# Temp_sensor_can.net
KiCad netlist of a schematic drawn in Altium Designer
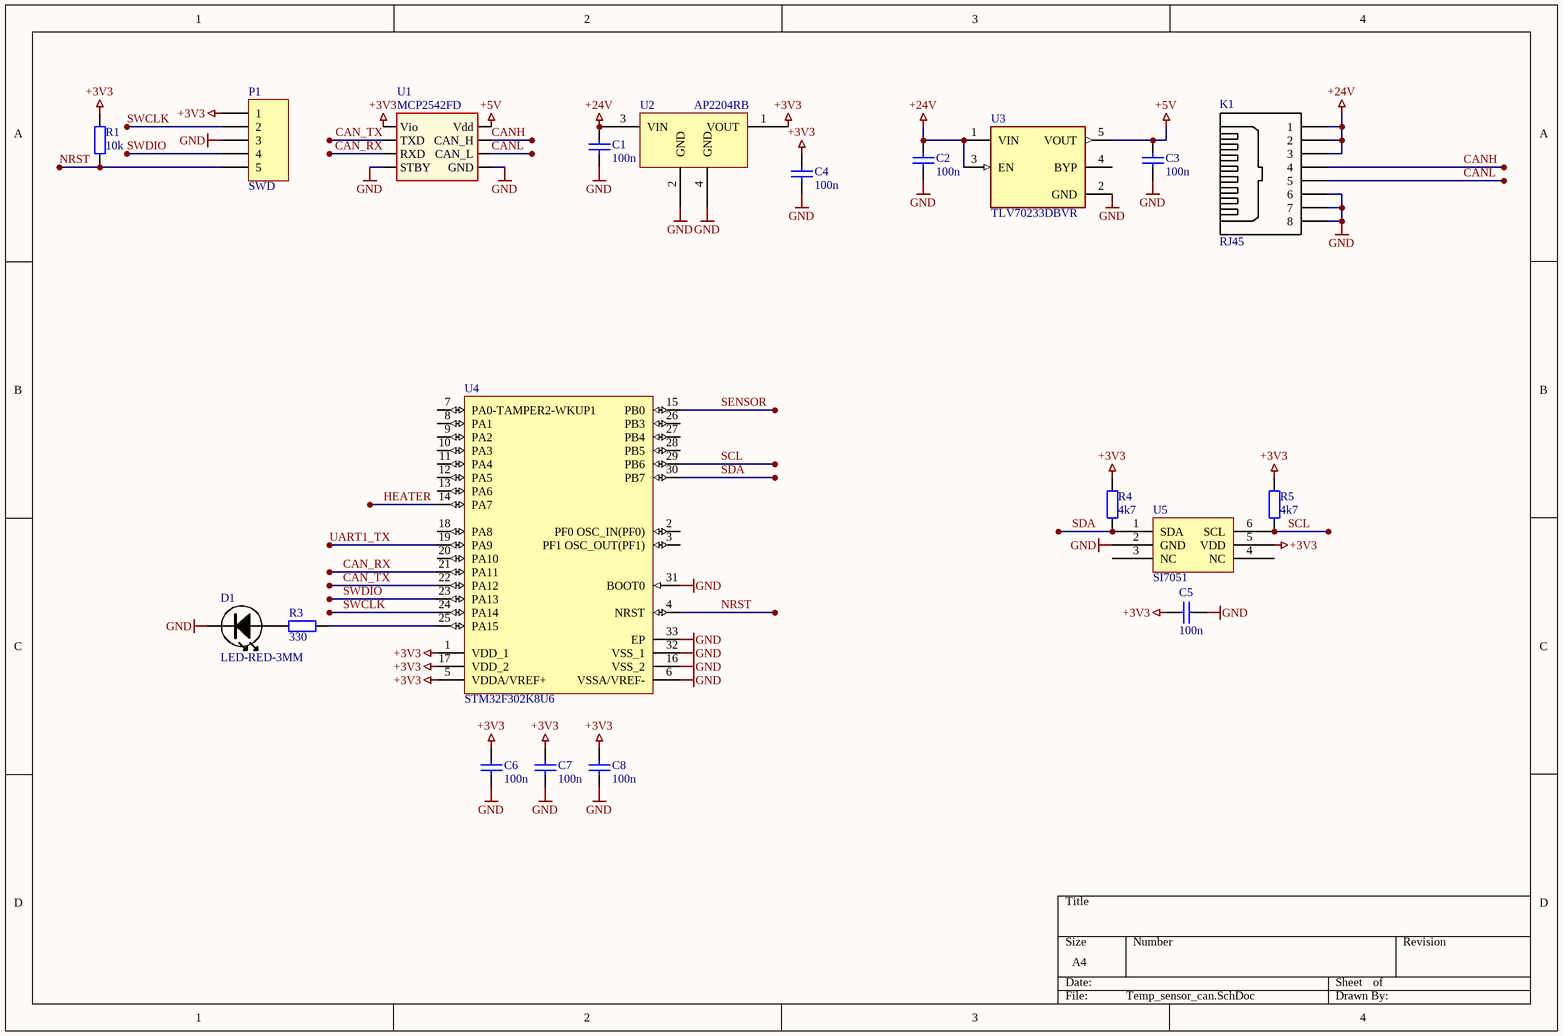
[diagram p0: Temp_sensor_can.SchDoc]

(export (version "E")
  (design (tool "Eeschema 10.0.6"))
  (components
    (comp (ref "C1")
      (value "100n")
      (footprint "0603C-GENERIC")
      (description "Capacitor")
      (fields (field (name "Comment") "Cap") (field (name "PUBLISHER") "Altium Limited"))
      (libsource (lib "Miscellaneous Devices") (part "Cap"))
    )
    (comp (ref "C2")
      (value "100n")
      (footprint "0603C-GENERIC")
      (description "Capacitor")
      (fields (field (name "Comment") "Cap") (field (name "PUBLISHER") "Altium Limited"))
      (libsource (lib "Miscellaneous Devices") (part "Cap"))
    )
    (comp (ref "C3")
      (value "100n")
      (footprint "0603C-GENERIC")
      (description "Capacitor")
      (fields (field (name "Comment") "Cap") (field (name "PUBLISHER") "Altium Limited"))
      (libsource (lib "Miscellaneous Devices") (part "Cap"))
    )
    (comp (ref "C4")
      (value "100n")
      (footprint "0603C-GENERIC")
      (description "Capacitor")
      (fields (field (name "Comment") "Cap") (field (name "PUBLISHER") "Altium Limited"))
      (libsource (lib "Miscellaneous Devices") (part "Cap"))
    )
    (comp (ref "C5")
      (value "100n")
      (footprint "0603C-GENERIC")
      (description "Capacitor")
      (fields (field (name "Comment") "Cap") (field (name "PUBLISHER") "Altium Limited"))
      (libsource (lib "Miscellaneous Devices") (part "Cap"))
    )
    (comp (ref "C6")
      (value "100n")
      (footprint "0603C-GENERIC")
      (description "Capacitor")
      (fields (field (name "Comment") "Cap") (field (name "PUBLISHER") "Altium Limited"))
      (libsource (lib "Miscellaneous Devices") (part "Cap"))
    )
    (comp (ref "C7")
      (value "100n")
      (footprint "0603C-GENERIC")
      (description "Capacitor")
      (fields (field (name "Comment") "Cap") (field (name "PUBLISHER") "Altium Limited"))
      (libsource (lib "Miscellaneous Devices") (part "Cap"))
    )
    (comp (ref "C8")
      (value "100n")
      (footprint "0603C-GENERIC")
      (description "Capacitor")
      (fields (field (name "Comment") "Cap") (field (name "PUBLISHER") "Altium Limited"))
      (libsource (lib "Miscellaneous Devices") (part "Cap"))
    )
    (comp (ref "D1")
      (value "LED-RED-3MM")
      (footprint "LED-3MM-GREEN")
      (description "LED-GREEN-3MM")
      (libsource (lib "vh_altium_library") (part "LED-GREEN-3MM"))
    )
    (comp (ref "K1")
      (value "RJ45")
      (footprint "rj45 - edge")
      (libsource (lib "vh_altium_library") (part "RJ45"))
    )
    (comp (ref "P1")
      (value "SWD")
      (footprint "HDR1X5")
      (description "Header, 5-Pin")
      (fields (field (name "PUBLISHER") "Altium Limited"))
      (libsource (lib "Miscellaneous Connectors") (part "Header 5"))
    )
    (comp (ref "R1")
      (value "10k")
      (footprint "0603R-GENERIC")
      (description "Resistor")
      (fields (field (name "Comment") "Res2") (field (name "PUBLISHER") "Altium Limited"))
      (libsource (lib "") (part "Res2_1"))
    )
    (comp (ref "R3")
      (value "330")
      (footprint "0603R-GENERIC")
      (description "Resistor")
      (fields (field (name "Comment") "Res2") (field (name "PUBLISHER") "Altium Limited"))
      (libsource (lib "Miscellaneous Devices") (part "Res2"))
    )
    (comp (ref "R4")
      (value "4k7")
      (footprint "0603R-GENERIC")
      (description "Resistor")
      (fields (field (name "Comment") "Res2") (field (name "PUBLISHER") "Altium Limited"))
      (libsource (lib "") (part "Res2_1"))
    )
    (comp (ref "R5")
      (value "4k7")
      (footprint "0603R-GENERIC")
      (description "Resistor")
      (fields (field (name "Comment") "Res2") (field (name "PUBLISHER") "Altium Limited"))
      (libsource (lib "") (part "Res2_1"))
    )
    (comp (ref "U1") (value "MCP2542FD") (footprint "SO8") (libsource (lib "suciastky2") (part "MCP2542FD")))
    (comp (ref "U2") (value "AP2204RB") (footprint "SOT-89") (libsource (lib "lib") (part "AP2204RB")))
    (comp (ref "U3")
      (value "TLV70233DBVR")
      (footprint "FP-SOT25-IPC_B")
      (description "IC REG LINEAR 3.3V 150MA SOT23-5")
      (fields
        (field (name "MANUFACTURER PART NUMBER") "AP2202K-3.3TRG1")
        (field (name "OCTOPART") "https://octopart.com/ap2202k-3.3trg1-diodes+inc.-30954618")
      )
      (libsource (lib "Altium Content Vault") (part "CMP-12756-000010-1"))
    )
    (comp (ref "U4")
      (value "STM32F302K8U6")
      (footprint "UFQFPN32_M")
      (fields (field (name "MANUFACTURER") "STMicroelectronics"))
      (libsource (lib "Altium Content Vault") (part "STM-STM32F302X6_X8-UFQFPN-32"))
    )
    (comp (ref "U5") (value "SI7051") (footprint "DFN_6P") (libsource (lib "lib") (part "SI7051")))
  )
  (nets
    (net (code "1") (name "+3V3") (class "Default")
      (node (ref "C4") (pin "2") (pinfunction "2_2") (pintype "passive"))
      (node (ref "C5") (pin "2") (pinfunction "2_2") (pintype "passive"))
      (node (ref "C6") (pin "1") (pinfunction "1_1") (pintype "passive"))
      (node (ref "C7") (pin "1") (pinfunction "1_1") (pintype "passive"))
      (node (ref "C8") (pin "1") (pinfunction "1_1") (pintype "passive"))
      (node (ref "P1") (pin "1") (pinfunction "1_1") (pintype "passive"))
      (node (ref "R1") (pin "2") (pinfunction "2_2") (pintype "passive"))
      (node (ref "R4") (pin "2") (pinfunction "2_2") (pintype "passive"))
      (node (ref "R5") (pin "2") (pinfunction "2_2") (pintype "passive"))
      (node (ref "U1") (pin "5") (pinfunction "Vio_5") (pintype "passive"))
      (node (ref "U2") (pin "1") (pinfunction "VOUT_1") (pintype "passive"))
      (node (ref "U4") (pin "1") (pinfunction "VDD_1_1") (pintype "power_in"))
      (node (ref "U4") (pin "17") (pinfunction "VDD_2_17") (pintype "power_in"))
      (node (ref "U4") (pin "5") (pinfunction "VDDA/VREF+_5") (pintype "power_in"))
      (node (ref "U5") (pin "5") (pinfunction "VDD_5") (pintype "passive"))
    )
    (net (code "2") (name "+5V") (class "Default")
      (node (ref "C3") (pin "2") (pinfunction "2_2") (pintype "passive"))
      (node (ref "U1") (pin "3") (pinfunction "Vdd_3") (pintype "passive"))
      (node (ref "U3") (pin "5") (pinfunction "VOUT_5") (pintype "output"))
    )
    (net (code "3") (name "+24V") (class "Default")
      (node (ref "C1") (pin "2") (pinfunction "2_2") (pintype "passive"))
      (node (ref "C2") (pin "2") (pinfunction "2_2") (pintype "passive"))
      (node (ref "K1") (pin "1") (pinfunction "1_1") (pintype "passive"))
      (node (ref "K1") (pin "2") (pinfunction "2_2") (pintype "passive"))
      (node (ref "K1") (pin "3") (pinfunction "3_3") (pintype "passive"))
      (node (ref "U2") (pin "3") (pinfunction "VIN_3") (pintype "passive"))
      (node (ref "U3") (pin "1") (pinfunction "VIN_1") (pintype "power_in"))
      (node (ref "U3") (pin "3") (pinfunction "EN_3") (pintype "input"))
    )
    (net (code "4") (name "/CANH") (class "Default")
      (node (ref "K1") (pin "4") (pinfunction "4_4") (pintype "passive"))
      (node (ref "U1") (pin "7") (pinfunction "CAN_H_7") (pintype "passive"))
    )
    (net (code "5") (name "/CANL") (class "Default")
      (node (ref "K1") (pin "5") (pinfunction "5_5") (pintype "passive"))
      (node (ref "U1") (pin "6") (pinfunction "CAN_L_6") (pintype "passive"))
    )
    (net (code "6") (name "/CAN_RX") (class "Default")
      (node (ref "U1") (pin "4") (pinfunction "RXD_4") (pintype "passive"))
      (node (ref "U4") (pin "21") (pinfunction "PA11_21") (pintype "bidirectional"))
    )
    (net (code "7") (name "/CAN_TX") (class "Default")
      (node (ref "U1") (pin "1") (pinfunction "TXD_1") (pintype "passive"))
      (node (ref "U4") (pin "22") (pinfunction "PA12_22") (pintype "bidirectional"))
    )
    (net (code "8") (name "/HEATER") (class "Default")
      (node (ref "U4") (pin "14") (pinfunction "PA7_14") (pintype "bidirectional"))
    )
    (net (code "9") (name "/NRST") (class "Default")
      (node (ref "P1") (pin "5") (pinfunction "5_5") (pintype "passive"))
      (node (ref "R1") (pin "1") (pinfunction "1_1") (pintype "passive"))
      (node (ref "U4") (pin "4") (pinfunction "NRST_4") (pintype "bidirectional"))
    )
    (net (code "10") (name "/SCL") (class "Default")
      (node (ref "R5") (pin "1") (pinfunction "1_1") (pintype "passive"))
      (node (ref "U4") (pin "29") (pinfunction "PB6_29") (pintype "bidirectional"))
      (node (ref "U5") (pin "6") (pinfunction "SCL_6") (pintype "passive"))
    )
    (net (code "11") (name "/SDA") (class "Default")
      (node (ref "R4") (pin "1") (pinfunction "1_1") (pintype "passive"))
      (node (ref "U4") (pin "30") (pinfunction "PB7_30") (pintype "bidirectional"))
      (node (ref "U5") (pin "1") (pinfunction "SDA_1") (pintype "passive"))
    )
    (net (code "12") (name "/SENSOR") (class "Default")
      (node (ref "U4") (pin "15") (pinfunction "PB0_15") (pintype "bidirectional"))
    )
    (net (code "13") (name "/SWCLK") (class "Default")
      (node (ref "P1") (pin "2") (pinfunction "2_2") (pintype "passive"))
      (node (ref "U4") (pin "24") (pinfunction "PA14_24") (pintype "bidirectional"))
    )
    (net (code "14") (name "/SWDIO") (class "Default")
      (node (ref "P1") (pin "4") (pinfunction "4_4") (pintype "passive"))
      (node (ref "U4") (pin "23") (pinfunction "PA13_23") (pintype "bidirectional"))
    )
    (net (code "15") (name "/UART1_TX") (class "Default")
      (node (ref "U4") (pin "19") (pinfunction "PA9_19") (pintype "bidirectional"))
    )
    (net (code "16") (name "GND") (class "Default")
      (node (ref "C1") (pin "1") (pinfunction "1_1") (pintype "passive"))
      (node (ref "C2") (pin "1") (pinfunction "1_1") (pintype "passive"))
      (node (ref "C3") (pin "1") (pinfunction "1_1") (pintype "passive"))
      (node (ref "C4") (pin "1") (pinfunction "1_1") (pintype "passive"))
      (node (ref "C5") (pin "1") (pinfunction "1_1") (pintype "passive"))
      (node (ref "C6") (pin "2") (pinfunction "2_2") (pintype "passive"))
      (node (ref "C7") (pin "2") (pinfunction "2_2") (pintype "passive"))
      (node (ref "C8") (pin "2") (pinfunction "2_2") (pintype "passive"))
      (node (ref "D1") (pin "K") (pintype "passive"))
      (node (ref "K1") (pin "6") (pinfunction "6_6") (pintype "passive"))
      (node (ref "K1") (pin "7") (pinfunction "7_7") (pintype "passive"))
      (node (ref "K1") (pin "8") (pinfunction "8_8") (pintype "passive"))
      (node (ref "P1") (pin "3") (pinfunction "3_3") (pintype "passive"))
      (node (ref "U1") (pin "2") (pinfunction "GND_2") (pintype "passive"))
      (node (ref "U1") (pin "8") (pinfunction "STBY_8") (pintype "passive"))
      (node (ref "U2") (pin "2") (pinfunction "GND_2") (pintype "passive"))
      (node (ref "U2") (pin "4") (pinfunction "GND_4") (pintype "passive"))
      (node (ref "U3") (pin "2") (pinfunction "GND_2") (pintype "power_in"))
      (node (ref "U4") (pin "16") (pinfunction "VSS_2_16") (pintype "power_in"))
      (node (ref "U4") (pin "31") (pinfunction "BOOT0_31") (pintype "input"))
      (node (ref "U4") (pin "32") (pinfunction "VSS_1_32") (pintype "power_in"))
      (node (ref "U4") (pin "33") (pinfunction "EP_33") (pintype "passive"))
      (node (ref "U4") (pin "6") (pinfunction "VSSA/VREF-_6") (pintype "power_in"))
      (node (ref "U5") (pin "2") (pinfunction "GND_2") (pintype "passive"))
    )
    (net (code "17") (name "Net-(D1-PadA)") (class "Default")
      (node (ref "D1") (pin "A") (pintype "passive"))
      (node (ref "R3") (pin "1") (pinfunction "1_1") (pintype "passive"))
    )
    (net (code "18") (name "Net-(U4-PA15)") (class "Default")
      (node (ref "R3") (pin "2") (pinfunction "2_2") (pintype "passive"))
      (node (ref "U4") (pin "25") (pinfunction "PA15_25") (pintype "bidirectional"))
    )
    (net (code "19") (name "unconnected-(U3-BYP-Pad4)") (class "Default")
      (node (ref "U3") (pin "4") (pinfunction "BYP_4") (pintype "passive"))
    )
    (net (code "20") (name "unconnected-(U4-PA0-TAMPER2-WKUP1-Pad7)") (class "Default")
      (node (ref "U4") (pin "7") (pinfunction "PA0-TAMPER2-WKUP1_7") (pintype "bidirectional"))
    )
    (net (code "21") (name "unconnected-(U4-PA1-Pad8)") (class "Default")
      (node (ref "U4") (pin "8") (pinfunction "PA1_8") (pintype "bidirectional"))
    )
    (net (code "22") (name "unconnected-(U4-PA2-Pad9)") (class "Default")
      (node (ref "U4") (pin "9") (pinfunction "PA2_9") (pintype "bidirectional"))
    )
    (net (code "23") (name "unconnected-(U4-PA3-Pad10)") (class "Default")
      (node (ref "U4") (pin "10") (pinfunction "PA3_10") (pintype "bidirectional"))
    )
    (net (code "24") (name "unconnected-(U4-PA4-Pad11)") (class "Default")
      (node (ref "U4") (pin "11") (pinfunction "PA4_11") (pintype "bidirectional"))
    )
    (net (code "25") (name "unconnected-(U4-PA5-Pad12)") (class "Default")
      (node (ref "U4") (pin "12") (pinfunction "PA5_12") (pintype "bidirectional"))
    )
    (net (code "26") (name "unconnected-(U4-PA6-Pad13)") (class "Default")
      (node (ref "U4") (pin "13") (pinfunction "PA6_13") (pintype "bidirectional"))
    )
    (net (code "27") (name "unconnected-(U4-PA8-Pad18)") (class "Default")
      (node (ref "U4") (pin "18") (pinfunction "PA8_18") (pintype "bidirectional"))
    )
    (net (code "28") (name "unconnected-(U4-PA10-Pad20)") (class "Default")
      (node (ref "U4") (pin "20") (pinfunction "PA10_20") (pintype "bidirectional"))
    )
    (net (code "29") (name "unconnected-(U4-PB3-Pad26)") (class "Default")
      (node (ref "U4") (pin "26") (pinfunction "PB3_26") (pintype "bidirectional"))
    )
    (net (code "30") (name "unconnected-(U4-PB4-Pad27)") (class "Default")
      (node (ref "U4") (pin "27") (pinfunction "PB4_27") (pintype "bidirectional"))
    )
    (net (code "31") (name "unconnected-(U4-PB5-Pad28)") (class "Default")
      (node (ref "U4") (pin "28") (pinfunction "PB5_28") (pintype "bidirectional"))
    )
    (net (code "32") (name "unconnected-(U4-PF0_OSC_IN(PF0)-Pad2)") (class "Default")
      (node (ref "U4") (pin "2") (pinfunction "PF0_OSC_IN(PF0)_2") (pintype "bidirectional"))
    )
    (net (code "33") (name "unconnected-(U4-PF1_OSC_OUT(PF1)-Pad3)") (class "Default")
      (node (ref "U4") (pin "3") (pinfunction "PF1_OSC_OUT(PF1)_3") (pintype "bidirectional"))
    )
    (net (code "34") (name "unconnected-(U5-NC-Pad3)") (class "Default")
      (node (ref "U5") (pin "3") (pinfunction "NC_3") (pintype "passive"))
    )
    (net (code "35") (name "unconnected-(U5-NC-Pad4)") (class "Default")
      (node (ref "U5") (pin "4") (pinfunction "NC_4") (pintype "passive"))
    )
  )
)
